# CATS-FAT-MCU.net
KiCad netlist of a schematic drawn in Altium Designer
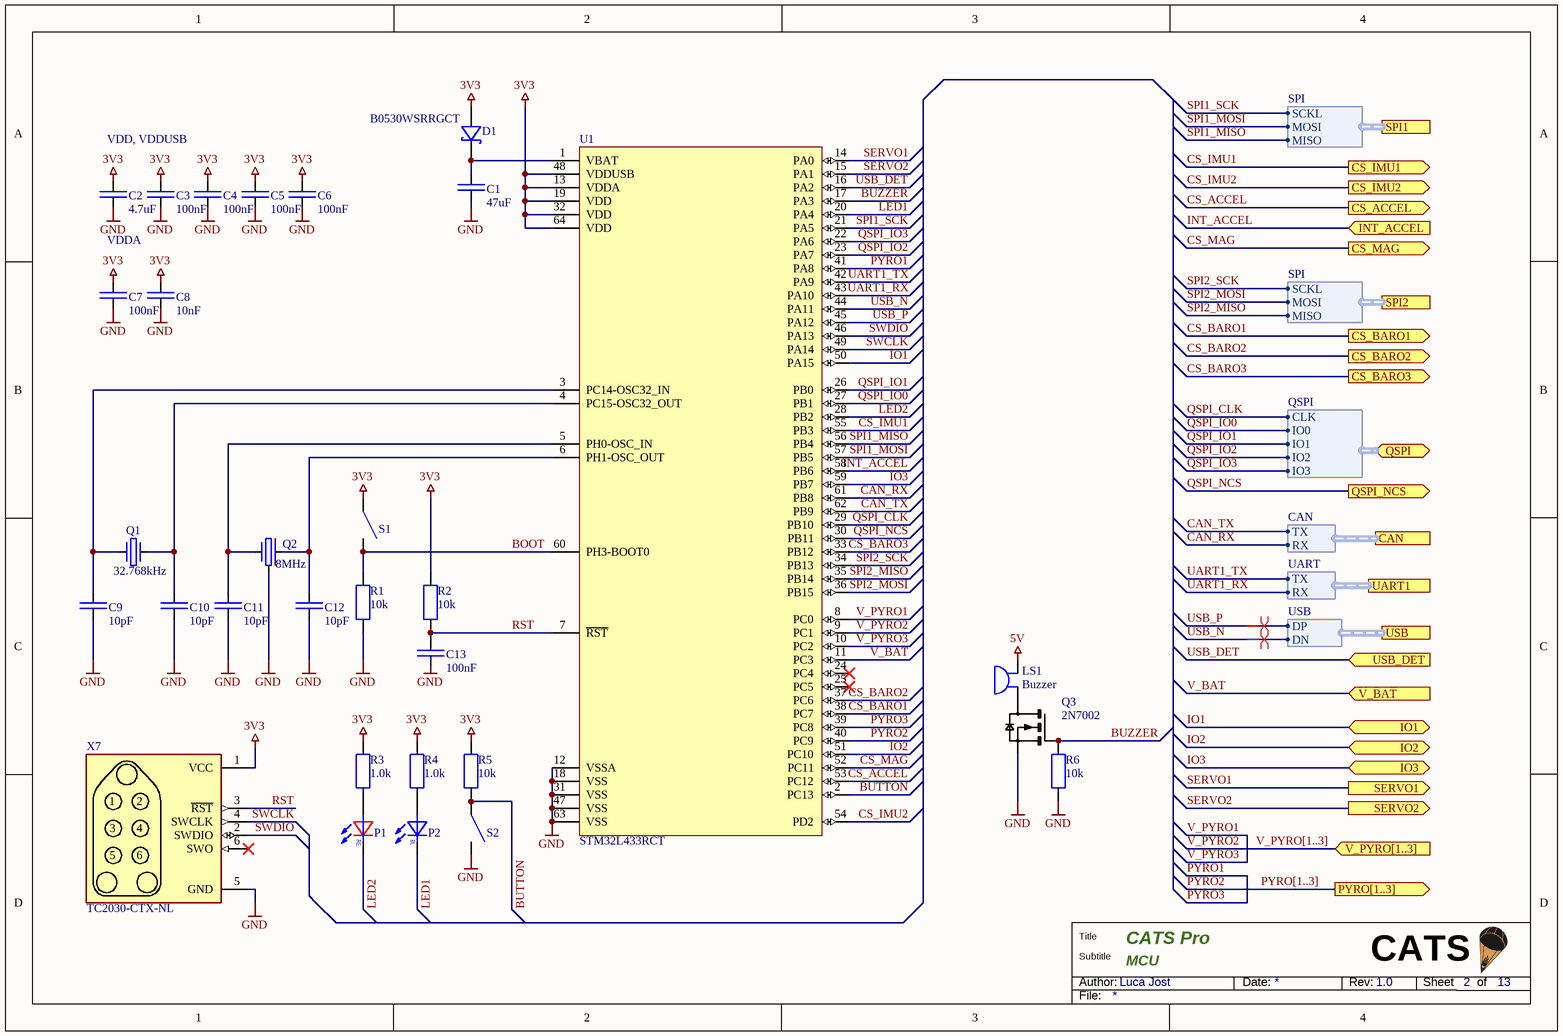
[diagram p0: CATS-FAT-MCU.SchDoc]

(export (version "E")
  (design (tool "Eeschema 10.0.6"))
  (components
    (comp (ref "C1")
      (value "47uF")
      (footprint "SMD Keramikkondensator 0805")
      (description "SMD Ceramic Capacitor E6")
      (libsource (lib "Ceramic Capacitors-E6") (part "E6 - 47uF"))
    )
    (comp (ref "C2")
      (value "4.7uF")
      (footprint "SMD Keramikkondensator 0603")
      (description "SMD Ceramic Capacitor E6")
      (libsource (lib "Ceramic Capacitors-E6") (part "E6 - 4.7uF"))
    )
    (comp (ref "C3")
      (value "100nF")
      (footprint "SMD Keramikkondensator 0603")
      (description "SMD Ceramic Capacitor E6")
      (libsource (lib "Ceramic Capacitors-E6") (part "E6 - 100nF"))
    )
    (comp (ref "C4")
      (value "100nF")
      (footprint "SMD Keramikkondensator 0603")
      (description "SMD Ceramic Capacitor E6")
      (libsource (lib "Ceramic Capacitors-E6") (part "E6 - 100nF"))
    )
    (comp (ref "C5")
      (value "100nF")
      (footprint "SMD Keramikkondensator 0603")
      (description "SMD Ceramic Capacitor E6")
      (libsource (lib "Ceramic Capacitors-E6") (part "E6 - 100nF"))
    )
    (comp (ref "C6")
      (value "100nF")
      (footprint "SMD Keramikkondensator 0603")
      (description "SMD Ceramic Capacitor E6")
      (libsource (lib "Ceramic Capacitors-E6") (part "E6 - 100nF"))
    )
    (comp (ref "C7")
      (value "100nF")
      (footprint "SMD Keramikkondensator 0603")
      (description "SMD Ceramic Capacitor E6")
      (libsource (lib "Ceramic Capacitors-E6") (part "E6 - 100nF"))
    )
    (comp (ref "C8")
      (value "10nF")
      (footprint "SMD Keramikkondensator 0603")
      (description "SMD Ceramic Capacitor E6")
      (libsource (lib "Ceramic Capacitors-E6") (part "E6 - 10nF"))
    )
    (comp (ref "C9")
      (value "10pF")
      (footprint "SMD Keramikkondensator 0603")
      (description "SMD Ceramic Capacitor E6")
      (libsource (lib "Ceramic Capacitors-E6") (part "E6 - 10pF"))
    )
    (comp (ref "C10")
      (value "10pF")
      (footprint "SMD Keramikkondensator 0603")
      (description "SMD Ceramic Capacitor E6")
      (libsource (lib "Ceramic Capacitors-E6") (part "E6 - 10pF"))
    )
    (comp (ref "C11")
      (value "10pF")
      (footprint "SMD Keramikkondensator 0603")
      (description "SMD Ceramic Capacitor E6")
      (libsource (lib "Ceramic Capacitors-E6") (part "E6 - 10pF"))
    )
    (comp (ref "C12")
      (value "10pF")
      (footprint "SMD Keramikkondensator 0603")
      (description "SMD Ceramic Capacitor E6")
      (libsource (lib "Ceramic Capacitors-E6") (part "E6 - 10pF"))
    )
    (comp (ref "C13")
      (value "100nF")
      (footprint "SMD Keramikkondensator 0603")
      (description "SMD Ceramic Capacitor E6")
      (libsource (lib "Ceramic Capacitors-E6") (part "E6 - 100nF"))
    )
    (comp (ref "D1")
      (value "B0530WSRRGCT")
      (footprint "SMD Diode SOD-323F")
      (description "200mW, 0.47V Schottky Barrier Diode")
      (libsource (lib "Diodes") (part "B0530WSRRGCT"))
    )
    (comp (ref "LS1")
      (value "Buzzer")
      (footprint "SMD BUZZER CMT-8504")
      (description "Buzzers Indicator, Internally Driven Piezo 12V 10mA 3kHz 100dB @ 12V, 10cm Through Hole PC Pins")
      (libsource (lib "Other") (part "Buzzer"))
    )
    (comp (ref "P1")
      (value "LED")
      (footprint "SMD LED 0603")
      (description "Color LED")
      (libsource (lib "") (part "LED_1"))
    )
    (comp (ref "P2")
      (value "LED")
      (footprint "SMD LED 0603")
      (description "Color LED")
      (libsource (lib "Diodes") (part "LED"))
    )
    (comp (ref "Q1")
      (value "32.768kHz")
      (footprint "SMD Crystal 3.2x1.5x0.9")
      (description "CRYSTAL 32.7680KHZ 9PF SMD")
      (libsource (lib "Other") (part "Crystal 32.768kHz"))
    )
    (comp (ref "Q2")
      (value "8MHz")
      (footprint "SMD Crystal 3.2X2.5X0.8")
      (description "SMD Crystal Resonators 8MHz ±10ppm SMD,3.2x2.5mm")
      (libsource (lib "Other") (part "Crystal"))
    )
    (comp (ref "Q3")
      (value "2N7002")
      (footprint "SMD MOSFET SOT-23")
      (description "MOSFET N-Channel 20V / 115mA")
      (libsource (lib "Electronic Switches") (part "2N7002"))
    )
    (comp (ref "R1")
      (value "10k")
      (footprint "SMD Widerstand 0603")
      (description "SMD Chip Resistor E24")
      (libsource (lib "Resistors-E24") (part "E24 - 10k"))
    )
    (comp (ref "R2")
      (value "10k")
      (footprint "SMD Widerstand 0603")
      (description "SMD Chip Resistor E24")
      (libsource (lib "Resistors-E24") (part "E24 - 10k"))
    )
    (comp (ref "R3")
      (value "1.0k")
      (footprint "SMD Widerstand 0603")
      (description "SMD Chip Resistor E24")
      (libsource (lib "Resistors-E24") (part "E24 - 1.0k"))
    )
    (comp (ref "R4")
      (value "1.0k")
      (footprint "SMD Widerstand 0603")
      (description "SMD Chip Resistor E24")
      (libsource (lib "Resistors-E24") (part "E24 - 1.0k"))
    )
    (comp (ref "R5")
      (value "10k")
      (footprint "SMD Widerstand 0603")
      (description "SMD Chip Resistor E24")
      (libsource (lib "Resistors-E24") (part "E24 - 10k"))
    )
    (comp (ref "R6")
      (value "10k")
      (footprint "SMD Widerstand 0603")
      (description "SMD Chip Resistor E24")
      (libsource (lib "Resistors-E24") (part "E24 - 10k"))
    )
    (comp (ref "S1")
      (value "SMD-Button")
      (footprint "SMD Button 2.5x3x1.2")
      (description "Button SPST")
      (libsource (lib "Switches") (part "Button 3mmx2.5mm"))
    )
    (comp (ref "S2")
      (value "SMD-Button")
      (footprint "SMD Button 2.5x3x1.2")
      (description "Button SPST")
      (libsource (lib "Switches") (part "Button 3mmx2.5mm"))
    )
    (comp (ref "U1")
      (value "STM32L433RCT")
      (footprint "SMD IC LQFP64-N")
      (description "ARM® Cortex®-M4 series Microcontroller IC 32-Bit 80MHz 256KB (256K x 8) FLASH 64-LQFP (10x10)")
      (libsource (lib "Microcontrollers") (part "STM32L433RCT"))
    )
    (comp (ref "X7")
      (value "TC2030-CTX-NL")
      (footprint "SMD Connector TC2030 w/ holes")
      (description "Tag-Connect for ARM-Cortex (6-Pin)")
      (libsource (lib "Connectors") (part "TC2030-CTX-NL"))
    )
  )
  (nets
    (net (code "6") (name "/BOOT") (class "Default")
      (node (ref "R1") (pin "2") (pinfunction "2_2") (pintype "passive"))
      (node (ref "S1") (pin "2") (pinfunction "2_2") (pintype "passive"))
      (node (ref "U1") (pin "60") (pinfunction "PH3-BOOT0_60") (pintype "passive"))
    )
    (net (code "7") (name "/BUTTON") (class "Default")
      (node (ref "R5") (pin "1") (pinfunction "1_1") (pintype "passive"))
      (node (ref "S2") (pin "1") (pinfunction "1_1") (pintype "passive"))
      (node (ref "U1") (pin "2") (pinfunction "PC13_2") (pintype "bidirectional"))
    )
    (net (code "8") (name "/BUZZER") (class "Default")
      (node (ref "Q3") (pin "G") (pinfunction "G_G") (pintype "passive"))
      (node (ref "R6") (pin "2") (pinfunction "2_2") (pintype "passive"))
      (node (ref "U1") (pin "17") (pinfunction "PA3_17") (pintype "bidirectional"))
    )
    (net (code "9") (name "/CAN_RX") (class "Default")
      (node (ref "U1") (pin "61") (pinfunction "PB8_61") (pintype "bidirectional"))
    )
    (net (code "10") (name "/CAN_TX") (class "Default")
      (node (ref "U1") (pin "62") (pinfunction "PB9_62") (pintype "bidirectional"))
    )
    (net (code "11") (name "/CS_ACCEL") (class "Default")
      (node (ref "U1") (pin "53") (pinfunction "PC12_53") (pintype "bidirectional"))
    )
    (net (code "12") (name "/CS_BARO1") (class "Default")
      (node (ref "U1") (pin "38") (pinfunction "PC7_38") (pintype "bidirectional"))
    )
    (net (code "13") (name "/CS_BARO2") (class "Default")
      (node (ref "U1") (pin "37") (pinfunction "PC6_37") (pintype "bidirectional"))
    )
    (net (code "14") (name "/CS_BARO3") (class "Default")
      (node (ref "U1") (pin "33") (pinfunction "PB12_33") (pintype "bidirectional"))
    )
    (net (code "15") (name "/CS_IMU1") (class "Default")
      (node (ref "U1") (pin "55") (pinfunction "PB3_55") (pintype "bidirectional"))
    )
    (net (code "16") (name "/CS_IMU2") (class "Default")
      (node (ref "U1") (pin "54") (pinfunction "PD2_54") (pintype "bidirectional"))
    )
    (net (code "17") (name "/CS_MAG") (class "Default")
      (node (ref "U1") (pin "52") (pinfunction "PC11_52") (pintype "bidirectional"))
    )
    (net (code "18") (name "/INT_ACCEL") (class "Default")
      (node (ref "U1") (pin "58") (pinfunction "PB6_58") (pintype "bidirectional"))
    )
    (net (code "19") (name "/IO1") (class "Default")
      (node (ref "U1") (pin "50") (pinfunction "PA15_50") (pintype "bidirectional"))
    )
    (net (code "20") (name "/IO2") (class "Default")
      (node (ref "U1") (pin "51") (pinfunction "PC10_51") (pintype "bidirectional"))
    )
    (net (code "21") (name "/IO3") (class "Default")
      (node (ref "U1") (pin "59") (pinfunction "PB7_59") (pintype "bidirectional"))
    )
    (net (code "22") (name "/LED1") (class "Default")
      (node (ref "P2") (pin "K") (pinfunction "K_K") (pintype "passive"))
      (node (ref "U1") (pin "20") (pinfunction "PA4_20") (pintype "bidirectional"))
    )
    (net (code "23") (name "/LED2") (class "Default")
      (node (ref "P1") (pin "K") (pinfunction "K_K") (pintype "passive"))
      (node (ref "U1") (pin "28") (pinfunction "PB2_28") (pintype "bidirectional"))
    )
    (net (code "24") (name "/PYRO1") (class "Default")
      (node (ref "U1") (pin "41") (pinfunction "PA8_41") (pintype "bidirectional"))
    )
    (net (code "25") (name "/PYRO2") (class "Default")
      (node (ref "U1") (pin "40") (pinfunction "PC9_40") (pintype "bidirectional"))
    )
    (net (code "26") (name "/PYRO3") (class "Default")
      (node (ref "U1") (pin "39") (pinfunction "PC8_39") (pintype "bidirectional"))
    )
    (net (code "28") (name "/QSPI_CLK") (class "Default")
      (node (ref "U1") (pin "29") (pinfunction "PB10_29") (pintype "bidirectional"))
    )
    (net (code "29") (name "/QSPI_IO0") (class "Default")
      (node (ref "U1") (pin "27") (pinfunction "PB1_27") (pintype "bidirectional"))
    )
    (net (code "30") (name "/QSPI_IO1") (class "Default")
      (node (ref "U1") (pin "26") (pinfunction "PB0_26") (pintype "bidirectional"))
    )
    (net (code "31") (name "/QSPI_IO2") (class "Default")
      (node (ref "U1") (pin "23") (pinfunction "PA7_23") (pintype "bidirectional"))
    )
    (net (code "32") (name "/QSPI_IO3") (class "Default")
      (node (ref "U1") (pin "22") (pinfunction "PA6_22") (pintype "bidirectional"))
    )
    (net (code "33") (name "/QSPI_NCS") (class "Default")
      (node (ref "U1") (pin "30") (pinfunction "PB11_30") (pintype "bidirectional"))
    )
    (net (code "34") (name "/RST") (class "Default")
      (node (ref "C13") (pin "2") (pinfunction "2_2") (pintype "passive"))
      (node (ref "R2") (pin "1") (pinfunction "1_1") (pintype "passive"))
      (node (ref "U1") (pin "7") (pinfunction "~{RST}_7") (pintype "passive"))
      (node (ref "X7") (pin "3") (pinfunction "~{RST}_3") (pintype "output"))
    )
    (net (code "35") (name "/SERVO1") (class "Default")
      (node (ref "U1") (pin "14") (pinfunction "PA0_14") (pintype "bidirectional"))
    )
    (net (code "36") (name "/SERVO2") (class "Default")
      (node (ref "U1") (pin "15") (pinfunction "PA1_15") (pintype "bidirectional"))
    )
    (net (code "37") (name "/SPI1_MISO") (class "Default")
      (node (ref "U1") (pin "56") (pinfunction "PB4_56") (pintype "bidirectional"))
    )
    (net (code "38") (name "/SPI1_MOSI") (class "Default")
      (node (ref "U1") (pin "57") (pinfunction "PB5_57") (pintype "bidirectional"))
    )
    (net (code "39") (name "/SPI1_SCK") (class "Default")
      (node (ref "U1") (pin "21") (pinfunction "PA5_21") (pintype "bidirectional"))
    )
    (net (code "40") (name "/SPI2_MISO") (class "Default")
      (node (ref "U1") (pin "35") (pinfunction "PB14_35") (pintype "bidirectional"))
    )
    (net (code "41") (name "/SPI2_MOSI") (class "Default")
      (node (ref "U1") (pin "36") (pinfunction "PB15_36") (pintype "bidirectional"))
    )
    (net (code "42") (name "/SPI2_SCK") (class "Default")
      (node (ref "U1") (pin "34") (pinfunction "PB13_34") (pintype "bidirectional"))
    )
    (net (code "43") (name "/SWCLK") (class "Default")
      (node (ref "U1") (pin "49") (pinfunction "PA14_49") (pintype "bidirectional"))
      (node (ref "X7") (pin "4") (pinfunction "SWCLK_4") (pintype "output"))
    )
    (net (code "44") (name "/SWDIO") (class "Default")
      (node (ref "U1") (pin "46") (pinfunction "PA13_46") (pintype "bidirectional"))
      (node (ref "X7") (pin "2") (pinfunction "SWDIO_2") (pintype "bidirectional"))
    )
    (net (code "45") (name "/UART1_RX") (class "Default")
      (node (ref "U1") (pin "43") (pinfunction "PA10_43") (pintype "bidirectional"))
    )
    (net (code "46") (name "/UART1_TX") (class "Default")
      (node (ref "U1") (pin "42") (pinfunction "PA9_42") (pintype "bidirectional"))
    )
    (net (code "47") (name "/USB_DET") (class "Default")
      (node (ref "U1") (pin "16") (pinfunction "PA2_16") (pintype "bidirectional"))
    )
    (net (code "48") (name "/USB_N") (class "Default")
      (node (ref "U1") (pin "44") (pinfunction "PA11_44") (pintype "bidirectional"))
    )
    (net (code "49") (name "/USB_P") (class "Default")
      (node (ref "U1") (pin "45") (pinfunction "PA12_45") (pintype "bidirectional"))
    )
    (net (code "50") (name "/V_BAT") (class "Default")
      (node (ref "U1") (pin "11") (pinfunction "PC3_11") (pintype "bidirectional"))
    )
    (net (code "51") (name "/V_PYRO1") (class "Default")
      (node (ref "U1") (pin "8") (pinfunction "PC0_8") (pintype "bidirectional"))
    )
    (net (code "52") (name "/V_PYRO2") (class "Default")
      (node (ref "U1") (pin "9") (pinfunction "PC1_9") (pintype "bidirectional"))
    )
    (net (code "53") (name "/V_PYRO3") (class "Default")
      (node (ref "U1") (pin "10") (pinfunction "PC2_10") (pintype "bidirectional"))
    )
    (net (code "60") (name "3V3") (class "Default")
      (node (ref "C2") (pin "2") (pinfunction "2_2") (pintype "passive"))
      (node (ref "C3") (pin "2") (pinfunction "2_2") (pintype "passive"))
      (node (ref "C4") (pin "2") (pinfunction "2_2") (pintype "passive"))
      (node (ref "C5") (pin "2") (pinfunction "2_2") (pintype "passive"))
      (node (ref "C6") (pin "2") (pinfunction "2_2") (pintype "passive"))
      (node (ref "C7") (pin "2") (pinfunction "2_2") (pintype "passive"))
      (node (ref "C8") (pin "2") (pinfunction "2_2") (pintype "passive"))
      (node (ref "D1") (pin "A") (pinfunction "A_A") (pintype "passive"))
      (node (ref "R2") (pin "2") (pinfunction "2_2") (pintype "passive"))
      (node (ref "R3") (pin "2") (pinfunction "2_2") (pintype "passive"))
      (node (ref "R4") (pin "2") (pinfunction "2_2") (pintype "passive"))
      (node (ref "R5") (pin "2") (pinfunction "2_2") (pintype "passive"))
      (node (ref "S1") (pin "1") (pinfunction "1_1") (pintype "passive"))
      (node (ref "U1") (pin "13") (pinfunction "VDDA_13") (pintype "passive"))
      (node (ref "U1") (pin "19") (pinfunction "VDD_19") (pintype "passive"))
      (node (ref "U1") (pin "32") (pinfunction "VDD_32") (pintype "passive"))
      (node (ref "U1") (pin "48") (pinfunction "VDDUSB_48") (pintype "passive"))
      (node (ref "U1") (pin "64") (pinfunction "VDD_64") (pintype "passive"))
      (node (ref "X7") (pin "1") (pinfunction "VCC_1") (pintype "power_in"))
    )
    (net (code "61") (name "5V") (class "Default")
      (node (ref "LS1") (pin "1") (pinfunction "1_1") (pintype "passive"))
    )
    (net (code "62") (name "GND") (class "Default")
      (node (ref "C1") (pin "1") (pinfunction "1_1") (pintype "passive"))
      (node (ref "C10") (pin "1") (pinfunction "1_1") (pintype "passive"))
      (node (ref "C11") (pin "1") (pinfunction "1_1") (pintype "passive"))
      (node (ref "C12") (pin "1") (pinfunction "1_1") (pintype "passive"))
      (node (ref "C13") (pin "1") (pinfunction "1_1") (pintype "passive"))
      (node (ref "C2") (pin "1") (pinfunction "1_1") (pintype "passive"))
      (node (ref "C3") (pin "1") (pinfunction "1_1") (pintype "passive"))
      (node (ref "C4") (pin "1") (pinfunction "1_1") (pintype "passive"))
      (node (ref "C5") (pin "1") (pinfunction "1_1") (pintype "passive"))
      (node (ref "C6") (pin "1") (pinfunction "1_1") (pintype "passive"))
      (node (ref "C7") (pin "1") (pinfunction "1_1") (pintype "passive"))
      (node (ref "C8") (pin "1") (pinfunction "1_1") (pintype "passive"))
      (node (ref "C9") (pin "1") (pinfunction "1_1") (pintype "passive"))
      (node (ref "Q2") (pin "3") (pinfunction "3_3") (pintype "power_in"))
      (node (ref "Q3") (pin "S") (pinfunction "S_S") (pintype "passive"))
      (node (ref "R1") (pin "1") (pinfunction "1_1") (pintype "passive"))
      (node (ref "R6") (pin "1") (pinfunction "1_1") (pintype "passive"))
      (node (ref "S2") (pin "2") (pinfunction "2_2") (pintype "passive"))
      (node (ref "U1") (pin "12") (pinfunction "VSSA_12") (pintype "passive"))
      (node (ref "U1") (pin "18") (pinfunction "VSS_18") (pintype "passive"))
      (node (ref "U1") (pin "31") (pinfunction "VSS_31") (pintype "passive"))
      (node (ref "U1") (pin "47") (pinfunction "VSS_47") (pintype "passive"))
      (node (ref "U1") (pin "63") (pinfunction "VSS_63") (pintype "passive"))
      (node (ref "X7") (pin "5") (pinfunction "GND_5") (pintype "power_in"))
    )
    (net (code "63") (name "Net-(LS1-Pad2)") (class "Default")
      (node (ref "LS1") (pin "2") (pinfunction "2_2") (pintype "passive"))
      (node (ref "Q3") (pin "D") (pinfunction "D_D") (pintype "passive"))
    )
    (net (code "64") (name "Net-(P1-PadA)") (class "Default")
      (node (ref "P1") (pin "A") (pinfunction "A_A") (pintype "passive"))
      (node (ref "R3") (pin "1") (pinfunction "1_1") (pintype "passive"))
    )
    (net (code "65") (name "Net-(P2-PadA)") (class "Default")
      (node (ref "P2") (pin "A") (pinfunction "A_A") (pintype "passive"))
      (node (ref "R4") (pin "1") (pinfunction "1_1") (pintype "passive"))
    )
    (net (code "66") (name "Net-(U1-PC14-OSC32_IN)") (class "Default")
      (node (ref "C9") (pin "2") (pinfunction "2_2") (pintype "passive"))
      (node (ref "Q1") (pin "1") (pinfunction "1_1") (pintype "passive"))
      (node (ref "U1") (pin "3") (pinfunction "PC14-OSC32_IN_3") (pintype "passive"))
    )
    (net (code "67") (name "Net-(U1-PC15-OSC32_OUT)") (class "Default")
      (node (ref "C10") (pin "2") (pinfunction "2_2") (pintype "passive"))
      (node (ref "Q1") (pin "2") (pinfunction "2_2") (pintype "passive"))
      (node (ref "U1") (pin "4") (pinfunction "PC15-OSC32_OUT_4") (pintype "passive"))
    )
    (net (code "68") (name "Net-(U1-PH0-OSC_IN)") (class "Default")
      (node (ref "C11") (pin "2") (pinfunction "2_2") (pintype "passive"))
      (node (ref "Q2") (pin "1") (pinfunction "1_1") (pintype "passive"))
      (node (ref "U1") (pin "5") (pinfunction "PH0-OSC_IN_5") (pintype "passive"))
    )
    (net (code "69") (name "Net-(U1-PH1-OSC_OUT)") (class "Default")
      (node (ref "C12") (pin "2") (pinfunction "2_2") (pintype "passive"))
      (node (ref "Q2") (pin "2") (pinfunction "2_2") (pintype "passive"))
      (node (ref "U1") (pin "6") (pinfunction "PH1-OSC_OUT_6") (pintype "passive"))
    )
    (net (code "70") (name "Net-(U1-VBAT)") (class "Default")
      (node (ref "C1") (pin "2") (pinfunction "2_2") (pintype "passive"))
      (node (ref "D1") (pin "K") (pinfunction "K_K") (pintype "passive"))
      (node (ref "U1") (pin "1") (pinfunction "VBAT_1") (pintype "passive"))
    )
    (net (code "71") (name "unconnected-(U1-PC4-Pad24)") (class "Default")
      (node (ref "U1") (pin "24") (pinfunction "PC4_24") (pintype "bidirectional+no_connect"))
    )
    (net (code "72") (name "unconnected-(U1-PC5-Pad25)") (class "Default")
      (node (ref "U1") (pin "25") (pinfunction "PC5_25") (pintype "bidirectional+no_connect"))
    )
    (net (code "73") (name "unconnected-(X7-SWO-Pad6)") (class "Default")
      (node (ref "X7") (pin "6") (pinfunction "SWO_6") (pintype "input+no_connect"))
    )
  )
)
